# Amp.net
KiCad netlist of a schematic drawn in Altium Designer
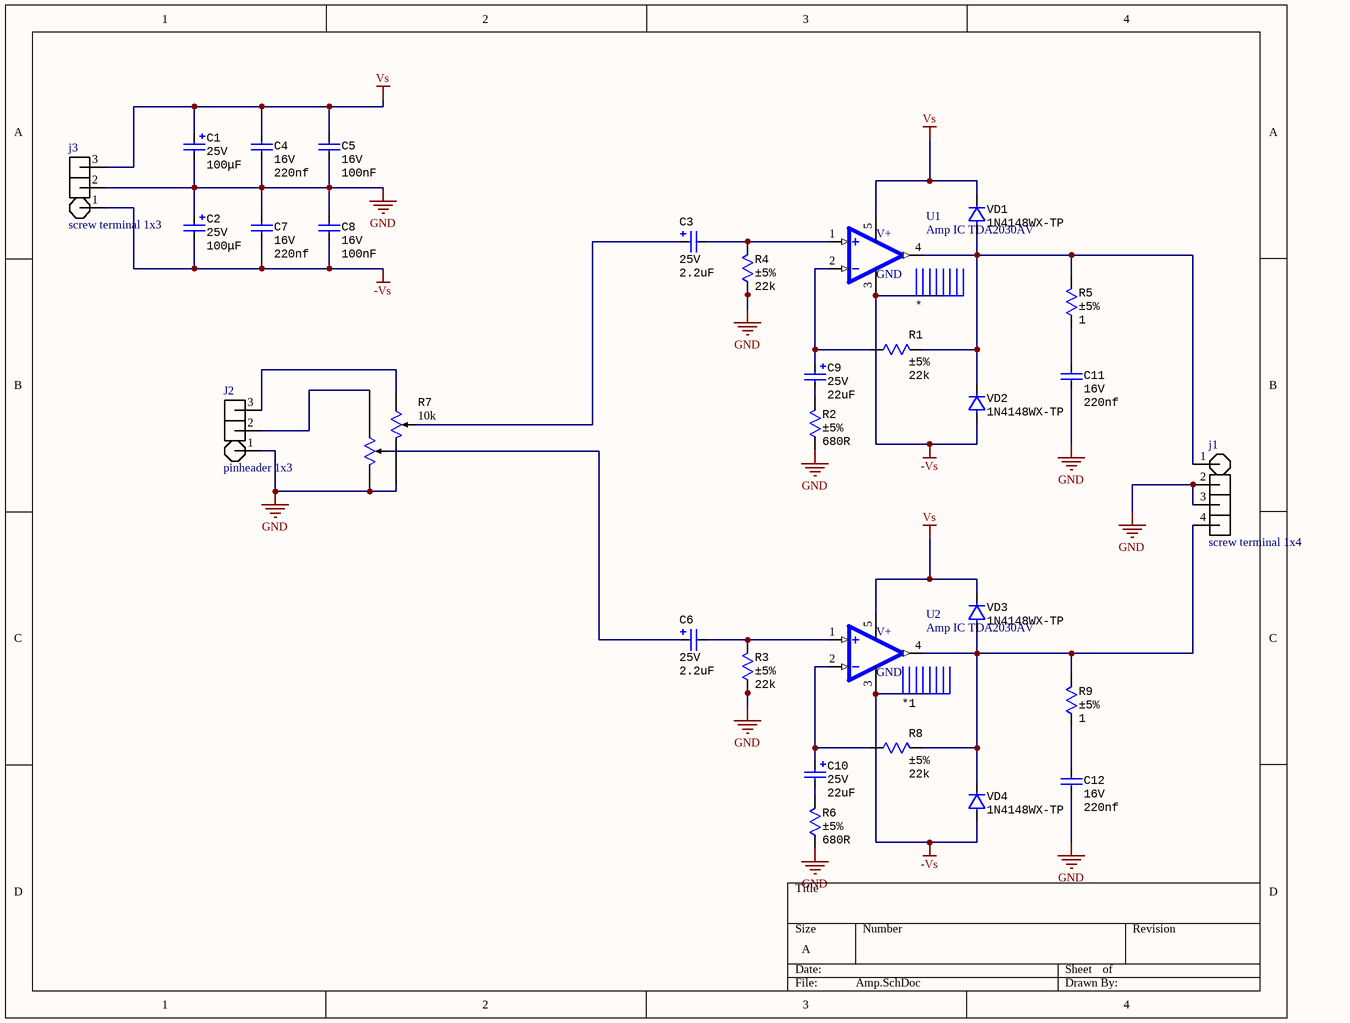
[diagram p0: Amp.SchDoc]

(export (version "E")
  (design (tool "Eeschema 10.0.6"))
  (components
    (comp (ref "*")
      (value "Heatsink 1 pad transistor TO220")
      (footprint "Heatsink 1 pad SK95-2M3")
      (libsource (lib "Heatsinks") (part "Heatsink 1 pad transistor TO220"))
    )
    (comp (ref "*1")
      (value "Heatsink 1 pad transistor TO220")
      (footprint "Heatsink 1 pad SK95-2M3")
      (libsource (lib "Heatsinks") (part "Heatsink 1 pad transistor TO220"))
    )
    (comp (ref "C1")
      (value "100μF")
      (footprint "CAP Electrolytic TH D8C3.5H12")
      (fields
        (field (name "MANUFACTURER") "Wurth")
        (field (name "PARTNUMBER") "860080475013")
        (field (name "VALUEMANUFACTURERPARTNUMBER") "Aluminium capacitor, 100μF, 25V, ±20%, 54mOhm, 14x10x5 mm, -55...+105°C")
        (field (name "VOLTAGE") "25V")
      )
      (libsource (lib "Passive") (part "Capacitor Aluminium"))
    )
    (comp (ref "C2")
      (value "100μF")
      (footprint "CAP Electrolytic TH D8C3.5H12")
      (fields
        (field (name "MANUFACTURER") "Wurth")
        (field (name "PARTNUMBER") "860080475013")
        (field (name "VALUEMANUFACTURERPARTNUMBER") "Aluminium capacitor, 100μF, 25V, ±20%, 54mOhm, 14x10x5 mm, -55...+105°C")
        (field (name "VOLTAGE") "25V")
      )
      (libsource (lib "Passive") (part "Capacitor Aluminium"))
    )
    (comp (ref "C3")
      (value "2.2uF")
      (footprint "CAP Electrolytic TH D6.3C2.5H11")
      (fields
        (field (name "MANUFACTURER") "Wurth")
        (field (name "PARTNUMBER") "860080475013")
        (field (name "VALUEMANUFACTURERPARTNUMBER") "Aluminium capacitor, 2.2uF, 25V, ±20%, 54mOhm, 14x10x5 mm, -55...+105°C")
        (field (name "VOLTAGE") "25V")
      )
      (libsource (lib "Passive") (part "Capacitor Aluminium"))
    )
    (comp (ref "C4")
      (value "220nf")
      (footprint "Cap ceramic TH C050-025X075")
      (fields
        (field (name "MANUFACTURER") "Yageo")
        (field (name "PARTNUMBER") "CC0201KRX7R7BB103")
        (field (name "VALUEMANUFACTURERPARTNUMBER") "Ceramic capacitor, 220nf, X7R, ±10%, 16V, 0201, -55...+125°C")
        (field (name "VOLTAGE") "16V")
      )
      (libsource (lib "Passive") (part "Capacitor Ceramic"))
    )
    (comp (ref "C5")
      (value "100nF")
      (footprint "Cap ceramic TH C025-024X044")
      (fields
        (field (name "MANUFACTURER") "Yageo")
        (field (name "PARTNUMBER") "CC0201KRX7R7BB103")
        (field (name "VALUEMANUFACTURERPARTNUMBER") "Ceramic capacitor, 100nF, X7R, ±10%, 16V, 0201, -55...+125°C")
        (field (name "VOLTAGE") "16V")
      )
      (libsource (lib "Passive") (part "Capacitor Ceramic"))
    )
    (comp (ref "C6")
      (value "2.2uF")
      (footprint "CAP Electrolytic TH D6.3C2.5H11")
      (fields
        (field (name "MANUFACTURER") "Wurth")
        (field (name "PARTNUMBER") "860080475013")
        (field (name "VALUEMANUFACTURERPARTNUMBER") "Aluminium capacitor, 2.2uF, 25V, ±20%, 54mOhm, 14x10x5 mm, -55...+105°C")
        (field (name "VOLTAGE") "25V")
      )
      (libsource (lib "Passive") (part "Capacitor Aluminium"))
    )
    (comp (ref "C7")
      (value "220nf")
      (footprint "Cap ceramic TH C050-025X075")
      (fields
        (field (name "MANUFACTURER") "Yageo")
        (field (name "PARTNUMBER") "CC0201KRX7R7BB103")
        (field (name "VALUEMANUFACTURERPARTNUMBER") "Ceramic capacitor, 220nf, X7R, ±10%, 16V, 0201, -55...+125°C")
        (field (name "VOLTAGE") "16V")
      )
      (libsource (lib "Passive") (part "Capacitor Ceramic"))
    )
    (comp (ref "C8")
      (value "100nF")
      (footprint "Cap ceramic TH C025-024X044")
      (fields
        (field (name "MANUFACTURER") "Yageo")
        (field (name "PARTNUMBER") "CC0201KRX7R7BB103")
        (field (name "VALUEMANUFACTURERPARTNUMBER") "Ceramic capacitor, 100nF, X7R, ±10%, 16V, 0201, -55...+125°C")
        (field (name "VOLTAGE") "16V")
      )
      (libsource (lib "Passive") (part "Capacitor Ceramic"))
    )
    (comp (ref "C9")
      (value "22uF")
      (footprint "CAP Electrolytic TH D5C2H11")
      (fields
        (field (name "MANUFACTURER") "Wurth")
        (field (name "PARTNUMBER") "860080475013")
        (field (name "VALUEMANUFACTURERPARTNUMBER") "Aluminium capacitor, 22uF, 25V, ±20%, 54mOhm, 14x10x5 mm, -55...+105°C")
        (field (name "VOLTAGE") "25V")
      )
      (libsource (lib "Passive") (part "Capacitor Aluminium"))
    )
    (comp (ref "C10")
      (value "22uF")
      (footprint "CAP Electrolytic TH D5C2H11")
      (fields
        (field (name "MANUFACTURER") "Wurth")
        (field (name "PARTNUMBER") "860080475013")
        (field (name "VALUEMANUFACTURERPARTNUMBER") "Aluminium capacitor, 22uF, 25V, ±20%, 54mOhm, 14x10x5 mm, -55...+105°C")
        (field (name "VOLTAGE") "25V")
      )
      (libsource (lib "Passive") (part "Capacitor Aluminium"))
    )
    (comp (ref "C11")
      (value "220nf")
      (footprint "Cap ceramic TH C050-025X075")
      (fields
        (field (name "MANUFACTURER") "Yageo")
        (field (name "PARTNUMBER") "CC0201KRX7R7BB103")
        (field (name "VALUEMANUFACTURERPARTNUMBER") "Ceramic capacitor, 220nf, X7R, ±10%, 16V, 0201, -55...+125°C")
        (field (name "VOLTAGE") "16V")
      )
      (libsource (lib "Passive") (part "Capacitor Ceramic"))
    )
    (comp (ref "C12")
      (value "220nf")
      (footprint "Cap ceramic TH C050-025X075")
      (fields
        (field (name "MANUFACTURER") "Yageo")
        (field (name "PARTNUMBER") "CC0201KRX7R7BB103")
        (field (name "VALUEMANUFACTURERPARTNUMBER") "Ceramic capacitor, 220nf, X7R, ±10%, 16V, 0201, -55...+125°C")
        (field (name "VOLTAGE") "16V")
      )
      (libsource (lib "Passive") (part "Capacitor Ceramic"))
    )
    (comp (ref "j1")
      (value "screw terminal 1x4")
      (footprint "screw terminal 1x4")
      (description "Conn Terminal Block 4 POS 5mm Solder ST Thru-Hole 10A Box")
      (fields
        (field (name "MANUFACTURER") "Weidmuller")
        (field (name "MANUFACTURER PART NUMBER") "1821490000")
      )
      (libsource (lib "connectors") (part "screw terminal 1x4"))
    )
    (comp (ref "J2")
      (value "pinheader 1x3")
      (footprint "Pin Header 1x3 TH Pitch 2.54mm")
      (fields
        (field (name "MANUFACTURER") "Samtec")
        (field (name "MANUFACTURER PART NUMBER") "TSW-103-07-F-S")
      )
      (libsource (lib "connectors") (part "pinheader 1x3"))
    )
    (comp (ref "j3")
      (value "screw terminal 1x3")
      (footprint "screw terminal 1x3")
      (description "PCB Terminal Block 3 Poles, 5 mm Pitch, 691101710003, Würth Elektronik")
      (fields
        (field (name "MANUFACTURER") "Wurth Electronics")
        (field (name "MANUFACTURER PART NUMBER") "691101710003")
      )
      (libsource (lib "connectors") (part "screw terminal 1x3"))
    )
    (comp (ref "R1")
      (value "22k")
      (footprint "RES TH 0.25W H 0207$10")
      (fields
        (field (name "MANUFACTURER") "Yageo")
        (field (name "PARTNUMBER") "RC0201JR-07100RL")
        (field (name "VALUEMANUFACTURERPARTNUMBER") "Resistor film, 22k, ±5%, 0201, 0.05W, -55...+125°C")
        (field (name "TOLERANCE") "±5%")
      )
      (libsource (lib "Passive") (part "Resistor Fixed"))
    )
    (comp (ref "R2")
      (value "680R")
      (footprint "RES TH 0.25W H 0207$10")
      (fields
        (field (name "MANUFACTURER") "Yageo")
        (field (name "PARTNUMBER") "RC0201JR-07100RL")
        (field (name "VALUEMANUFACTURERPARTNUMBER") "Resistor film, 680R, ±5%, 0201, 0.05W, -55...+125°C")
        (field (name "TOLERANCE") "±5%")
      )
      (libsource (lib "Passive") (part "Resistor Fixed"))
    )
    (comp (ref "R3")
      (value "22k")
      (footprint "RES TH 0.25W H 0207$10")
      (fields
        (field (name "MANUFACTURER") "Yageo")
        (field (name "PARTNUMBER") "RC0201JR-07100RL")
        (field (name "VALUEMANUFACTURERPARTNUMBER") "Resistor film, 22k, ±5%, 0201, 0.05W, -55...+125°C")
        (field (name "TOLERANCE") "±5%")
      )
      (libsource (lib "Passive") (part "Resistor Fixed"))
    )
    (comp (ref "R4")
      (value "22k")
      (footprint "RES TH 0.25W H 0207$10")
      (fields
        (field (name "MANUFACTURER") "Yageo")
        (field (name "PARTNUMBER") "RC0201JR-07100RL")
        (field (name "VALUEMANUFACTURERPARTNUMBER") "Resistor film, 22k, ±5%, 0201, 0.05W, -55...+125°C")
        (field (name "TOLERANCE") "±5%")
      )
      (libsource (lib "Passive") (part "Resistor Fixed"))
    )
    (comp (ref "R5")
      (value "1")
      (footprint "RES TH 0.25W H 0207$10")
      (fields
        (field (name "MANUFACTURER") "Yageo")
        (field (name "PARTNUMBER") "RC0201JR-07100RL")
        (field (name "VALUEMANUFACTURERPARTNUMBER") "Resistor film, 1, ±5%, 0201, 0.05W, -55...+125°C")
        (field (name "TOLERANCE") "±5%")
      )
      (libsource (lib "Passive") (part "Resistor Fixed"))
    )
    (comp (ref "R6")
      (value "680R")
      (footprint "RES TH 0.25W H 0207$10")
      (fields
        (field (name "MANUFACTURER") "Yageo")
        (field (name "PARTNUMBER") "RC0201JR-07100RL")
        (field (name "VALUEMANUFACTURERPARTNUMBER") "Resistor film, 680R, ±5%, 0201, 0.05W, -55...+125°C")
        (field (name "TOLERANCE") "±5%")
      )
      (libsource (lib "Passive") (part "Resistor Fixed"))
    )
    (comp (ref "R7")
      (value "10k")
      (footprint "Res VAR POT  TH 2 gang PDB182")
      (fields
        (field (name "MANUFACTURER") "Bourns")
        (field (name "PARTNUMBER") "3296W-1-103LF")
        (field (name "VALUEMANUFACTURERPARTNUMBER") "Resistor film, 10k, , 3296W, 0.5W, -55...+125°C")
      )
      (libsource (lib "Passive") (part "Resistor Potentiometer 2 Gang"))
    )
    (comp (ref "R8")
      (value "22k")
      (footprint "RES TH 0.25W H 0207$10")
      (fields
        (field (name "MANUFACTURER") "Yageo")
        (field (name "PARTNUMBER") "RC0201JR-07100RL")
        (field (name "VALUEMANUFACTURERPARTNUMBER") "Resistor film, 22k, ±5%, 0201, 0.05W, -55...+125°C")
        (field (name "TOLERANCE") "±5%")
      )
      (libsource (lib "Passive") (part "Resistor Fixed"))
    )
    (comp (ref "R9")
      (value "1")
      (footprint "RES TH 0.25W H 0207$10")
      (fields
        (field (name "MANUFACTURER") "Yageo")
        (field (name "PARTNUMBER") "RC0201JR-07100RL")
        (field (name "VALUEMANUFACTURERPARTNUMBER") "Resistor film, 1, ±5%, 0201, 0.05W, -55...+125°C")
        (field (name "TOLERANCE") "±5%")
      )
      (libsource (lib "Passive") (part "Resistor Fixed"))
    )
    (comp (ref "U1")
      (value "Amp IC TDA2030AV")
      (footprint "CB360")
      (description "STMICROELECTRONICS         TDA2030AV.             Audio Power Amplifier, 18 W, 5 Pins")
      (fields (field (name "MP") "TDA2030AV") (field (name "MF") "STMicroelectronics"))
      (libsource (lib "ICs") (part "Amp IC TDA2030AV"))
    )
    (comp (ref "U2")
      (value "Amp IC TDA2030AV")
      (footprint "CB360")
      (description "STMICROELECTRONICS         TDA2030AV.             Audio Power Amplifier, 18 W, 5 Pins")
      (fields (field (name "MP") "TDA2030AV") (field (name "MF") "STMicroelectronics"))
      (libsource (lib "ICs") (part "Amp IC TDA2030AV"))
    )
    (comp (ref "VD1")
      (value "~")
      (footprint "Diode TH DO-41 (h) (1n4007)")
      (fields
        (field (name "MANUFACTURER") "Micro Commercial")
        (field (name "VALUEMANUFACTURERPARTNUMBER") "Single diode, 75V, 150mA, 1V, 4ns, SOD-323, -55...+150°C")
        (field (name "VOLTAGE") "75V")
        (field (name "PARTNUMBER") "1N4148WX-TP")
      )
      (libsource (lib "diode") (part "Diode single"))
    )
    (comp (ref "VD2")
      (value "~")
      (footprint "Diode TH DO-41 (h) (1n4007)")
      (fields
        (field (name "MANUFACTURER") "Micro Commercial")
        (field (name "VALUEMANUFACTURERPARTNUMBER") "Single diode, 75V, 150mA, 1V, 4ns, SOD-323, -55...+150°C")
        (field (name "VOLTAGE") "75V")
        (field (name "PARTNUMBER") "1N4148WX-TP")
      )
      (libsource (lib "diode") (part "Diode single"))
    )
    (comp (ref "VD3")
      (value "~")
      (footprint "Diode TH DO-41 (h) (1n4007)")
      (fields
        (field (name "MANUFACTURER") "Micro Commercial")
        (field (name "VALUEMANUFACTURERPARTNUMBER") "Single diode, 75V, 150mA, 1V, 4ns, SOD-323, -55...+150°C")
        (field (name "VOLTAGE") "75V")
        (field (name "PARTNUMBER") "1N4148WX-TP")
      )
      (libsource (lib "diode") (part "Diode single"))
    )
    (comp (ref "VD4")
      (value "~")
      (footprint "Diode TH DO-41 (h) (1n4007)")
      (fields
        (field (name "MANUFACTURER") "Micro Commercial")
        (field (name "VALUEMANUFACTURERPARTNUMBER") "Single diode, 75V, 150mA, 1V, 4ns, SOD-323, -55...+150°C")
        (field (name "VOLTAGE") "75V")
        (field (name "PARTNUMBER") "1N4148WX-TP")
      )
      (libsource (lib "diode") (part "Diode single"))
    )
  )
  (nets
    (net (code "1") (name "-Vs") (class "Default")
      (node (ref "*") (pin "1") (pinfunction "S_1") (pintype "passive"))
      (node (ref "*1") (pin "1") (pinfunction "S_1") (pintype "passive"))
      (node (ref "C2") (pin "2") (pinfunction "2_2") (pintype "passive"))
      (node (ref "C7") (pin "2") (pinfunction "2_2") (pintype "passive"))
      (node (ref "C8") (pin "2") (pinfunction "2_2") (pintype "passive"))
      (node (ref "U1") (pin "3") (pinfunction "GND_3") (pintype "power_in"))
      (node (ref "U2") (pin "3") (pinfunction "GND_3") (pintype "power_in"))
      (node (ref "VD2") (pin "1") (pinfunction "1_1") (pintype "passive"))
      (node (ref "VD4") (pin "1") (pinfunction "1_1") (pintype "passive"))
      (node (ref "j3") (pin "1") (pinfunction "1_1") (pintype "passive"))
    )
    (net (code "2") (name "GND") (class "Default")
      (node (ref "C1") (pin "2") (pinfunction "2_2") (pintype "passive"))
      (node (ref "C11") (pin "2") (pinfunction "2_2") (pintype "passive"))
      (node (ref "C12") (pin "2") (pinfunction "2_2") (pintype "passive"))
      (node (ref "C2") (pin "1") (pinfunction "1_1") (pintype "passive"))
      (node (ref "C4") (pin "2") (pinfunction "2_2") (pintype "passive"))
      (node (ref "C5") (pin "2") (pinfunction "2_2") (pintype "passive"))
      (node (ref "C7") (pin "1") (pinfunction "1_1") (pintype "passive"))
      (node (ref "C8") (pin "1") (pinfunction "1_1") (pintype "passive"))
      (node (ref "J2") (pin "1") (pinfunction "1_1") (pintype "passive"))
      (node (ref "R2") (pin "1") (pinfunction "1_1") (pintype "passive"))
      (node (ref "R3") (pin "1") (pinfunction "1_1") (pintype "passive"))
      (node (ref "R4") (pin "1") (pinfunction "1_1") (pintype "passive"))
      (node (ref "R6") (pin "1") (pinfunction "1_1") (pintype "passive"))
      (node (ref "R7") (pin "1") (pinfunction "1_1") (pintype "passive"))
      (node (ref "R7") (pin "6") (pinfunction "6_6") (pintype "passive"))
      (node (ref "j1") (pin "2") (pinfunction "2_2") (pintype "passive"))
      (node (ref "j1") (pin "3") (pinfunction "3_3") (pintype "passive"))
      (node (ref "j3") (pin "2") (pinfunction "2_2") (pintype "passive"))
    )
    (net (code "3") (name "Net-(C3-Pad1)") (class "Default")
      (node (ref "C3") (pin "1") (pinfunction "1_1") (pintype "passive"))
      (node (ref "R7") (pin "5") (pinfunction "5_5") (pintype "passive"))
    )
    (net (code "4") (name "Net-(C6-Pad1)") (class "Default")
      (node (ref "C6") (pin "1") (pinfunction "1_1") (pintype "passive"))
      (node (ref "R7") (pin "2") (pinfunction "2_2") (pintype "passive"))
    )
    (net (code "5") (name "Net-(C9-Pad2)") (class "Default")
      (node (ref "C9") (pin "2") (pinfunction "2_2") (pintype "passive"))
      (node (ref "R2") (pin "2") (pinfunction "2_2") (pintype "passive"))
    )
    (net (code "6") (name "Net-(C10-Pad2)") (class "Default")
      (node (ref "C10") (pin "2") (pinfunction "2_2") (pintype "passive"))
      (node (ref "R6") (pin "2") (pinfunction "2_2") (pintype "passive"))
    )
    (net (code "7") (name "Net-(C11-Pad1)") (class "Default")
      (node (ref "C11") (pin "1") (pinfunction "1_1") (pintype "passive"))
      (node (ref "R5") (pin "1") (pinfunction "1_1") (pintype "passive"))
    )
    (net (code "8") (name "Net-(C12-Pad1)") (class "Default")
      (node (ref "C12") (pin "1") (pinfunction "1_1") (pintype "passive"))
      (node (ref "R9") (pin "1") (pinfunction "1_1") (pintype "passive"))
    )
    (net (code "9") (name "Net-(J2-Pad2)") (class "Default")
      (node (ref "J2") (pin "2") (pinfunction "2_2") (pintype "passive"))
      (node (ref "R7") (pin "3") (pinfunction "3_3") (pintype "passive"))
    )
    (net (code "10") (name "Net-(J2-Pad3)") (class "Default")
      (node (ref "J2") (pin "3") (pinfunction "3_3") (pintype "passive"))
      (node (ref "R7") (pin "4") (pinfunction "4_4") (pintype "passive"))
    )
    (net (code "11") (name "Net-(U1-+IN)") (class "Default")
      (node (ref "C3") (pin "2") (pinfunction "2_2") (pintype "passive"))
      (node (ref "R4") (pin "2") (pinfunction "2_2") (pintype "passive"))
      (node (ref "U1") (pin "1") (pinfunction "+IN_1") (pintype "input"))
    )
    (net (code "12") (name "Net-(U1--IN)") (class "Default")
      (node (ref "C9") (pin "1") (pinfunction "1_1") (pintype "passive"))
      (node (ref "R1") (pin "1") (pinfunction "1_1") (pintype "passive"))
      (node (ref "U1") (pin "2") (pinfunction "-IN_2") (pintype "input"))
    )
    (net (code "13") (name "Net-(U1-OUT)") (class "Default")
      (node (ref "R1") (pin "2") (pinfunction "2_2") (pintype "passive"))
      (node (ref "R5") (pin "2") (pinfunction "2_2") (pintype "passive"))
      (node (ref "U1") (pin "4") (pinfunction "OUT_4") (pintype "output"))
      (node (ref "VD1") (pin "1") (pinfunction "1_1") (pintype "passive"))
      (node (ref "VD2") (pin "2") (pinfunction "2_2") (pintype "passive"))
      (node (ref "j1") (pin "1") (pinfunction "1_1") (pintype "passive"))
    )
    (net (code "14") (name "Net-(U2-+IN)") (class "Default")
      (node (ref "C6") (pin "2") (pinfunction "2_2") (pintype "passive"))
      (node (ref "R3") (pin "2") (pinfunction "2_2") (pintype "passive"))
      (node (ref "U2") (pin "1") (pinfunction "+IN_1") (pintype "input"))
    )
    (net (code "15") (name "Net-(U2--IN)") (class "Default")
      (node (ref "C10") (pin "1") (pinfunction "1_1") (pintype "passive"))
      (node (ref "R8") (pin "1") (pinfunction "1_1") (pintype "passive"))
      (node (ref "U2") (pin "2") (pinfunction "-IN_2") (pintype "input"))
    )
    (net (code "16") (name "Net-(U2-OUT)") (class "Default")
      (node (ref "R8") (pin "2") (pinfunction "2_2") (pintype "passive"))
      (node (ref "R9") (pin "2") (pinfunction "2_2") (pintype "passive"))
      (node (ref "U2") (pin "4") (pinfunction "OUT_4") (pintype "output"))
      (node (ref "VD3") (pin "1") (pinfunction "1_1") (pintype "passive"))
      (node (ref "VD4") (pin "2") (pinfunction "2_2") (pintype "passive"))
      (node (ref "j1") (pin "4") (pinfunction "4_4") (pintype "passive"))
    )
    (net (code "17") (name "Vs") (class "Default")
      (node (ref "C1") (pin "1") (pinfunction "1_1") (pintype "passive"))
      (node (ref "C4") (pin "1") (pinfunction "1_1") (pintype "passive"))
      (node (ref "C5") (pin "1") (pinfunction "1_1") (pintype "passive"))
      (node (ref "U1") (pin "5") (pinfunction "V+_5") (pintype "power_in"))
      (node (ref "U2") (pin "5") (pinfunction "V+_5") (pintype "power_in"))
      (node (ref "VD1") (pin "2") (pinfunction "2_2") (pintype "passive"))
      (node (ref "VD3") (pin "2") (pinfunction "2_2") (pintype "passive"))
      (node (ref "j3") (pin "3") (pinfunction "3_3") (pintype "passive"))
    )
  )
)
